# lcd.net
KiCad netlist of a schematic drawn in EAGLE
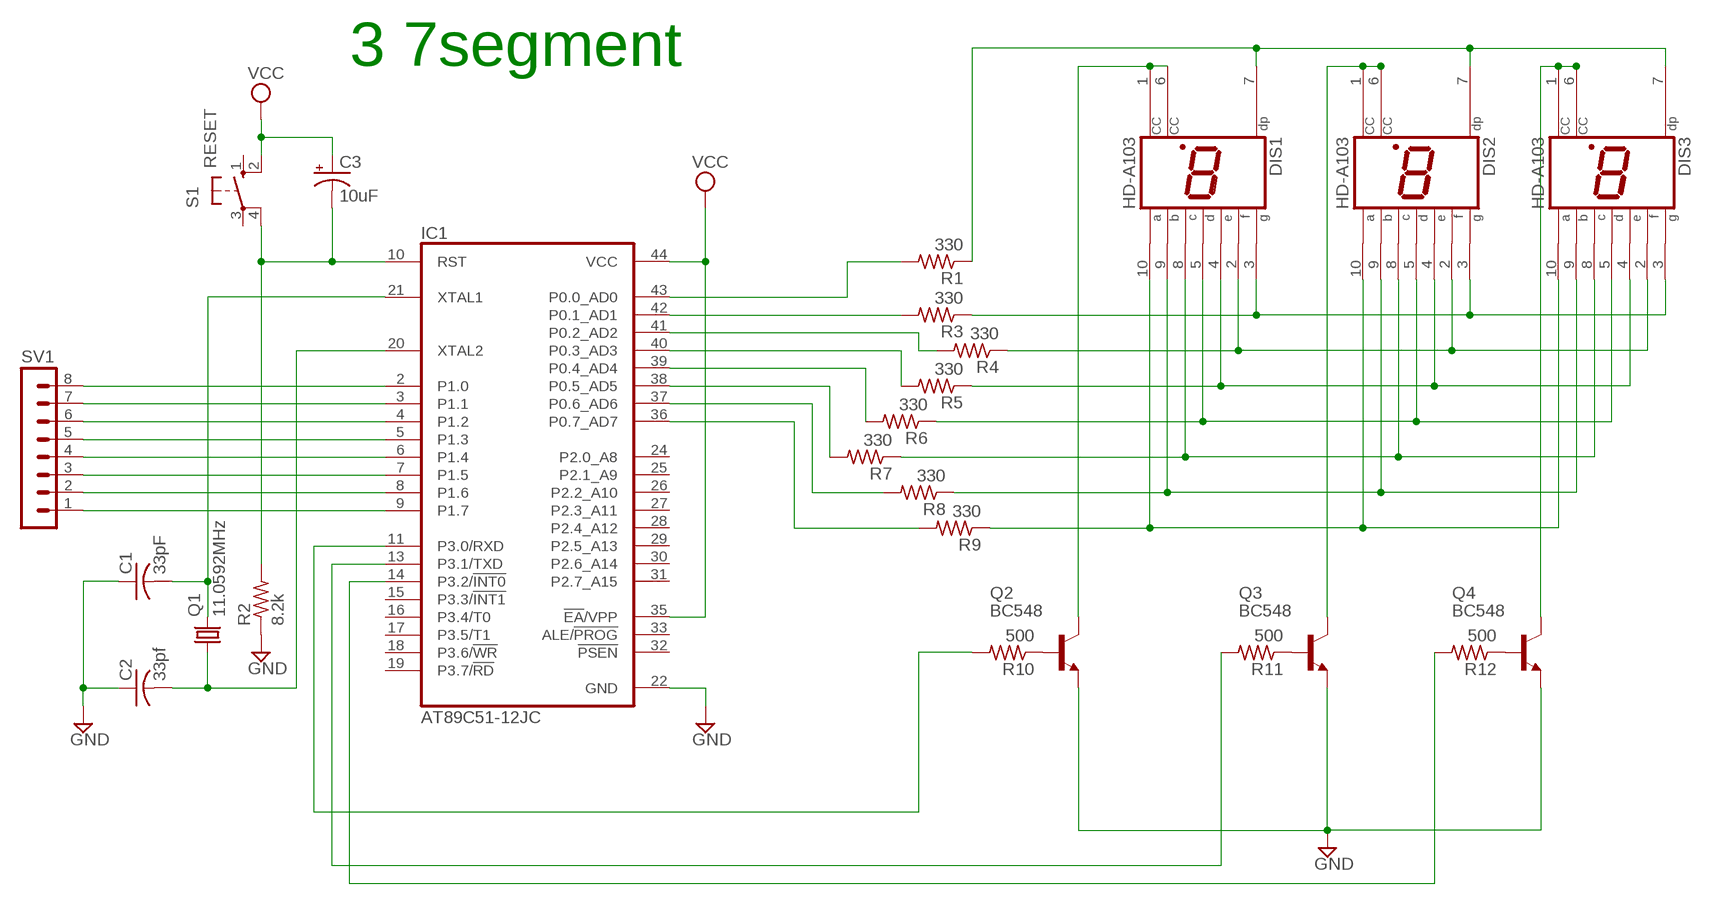
[diagram p0: schematic, sheet 1]

(export (version "E")
  (design (tool "Eeschema 10.0.6"))
  (components
    (comp (ref "C1")
      (value "33pF")
      (footprint "eagle-import:C025-025X050")
      (libsource (lib "eagle-import") (part "C-US025-025X050"))
    )
    (comp (ref "C2")
      (value "33pf")
      (footprint "eagle-import:C025-025X050")
      (libsource (lib "eagle-import") (part "C-US025-025X050"))
    )
    (comp (ref "C3")
      (value "10uF")
      (footprint "eagle-import:E2,5-5")
      (libsource (lib "eagle-import") (part "CPOL-USE2.5-5"))
    )
    (comp (ref "DIS1")
      (value "HD-A103")
      (footprint "eagle-import:HDSP-A")
      (libsource (lib "eagle-import") (part "HD-A103"))
    )
    (comp (ref "DIS2")
      (value "HD-A103")
      (footprint "eagle-import:HDSP-A")
      (libsource (lib "eagle-import") (part "HD-A103"))
    )
    (comp (ref "DIS3")
      (value "HD-A103")
      (footprint "eagle-import:HDSP-A")
      (libsource (lib "eagle-import") (part "HD-A103"))
    )
    (comp (ref "IC1")
      (value "AT89C51-12JC")
      (footprint "eagle-import:PLCC44")
      (fields (field (name "MPN") "AT89C51ED2-SLSUM"))
      (libsource (lib "eagle-import") (part "AT89C51-JC12"))
    )
    (comp (ref "Q1")
      (value "11.0592MHz")
      (footprint "eagle-import:TC26H")
      (libsource (lib "eagle-import") (part "CRYSTALTC26H"))
    )
    (comp (ref "Q2")
      (value "BC548")
      (footprint "eagle-import:TO92-EBC")
      (libsource (lib "eagle-import") (part "BC548"))
    )
    (comp (ref "Q3")
      (value "BC548")
      (footprint "eagle-import:TO92-EBC")
      (libsource (lib "eagle-import") (part "BC548"))
    )
    (comp (ref "Q4")
      (value "BC548")
      (footprint "eagle-import:TO92-EBC")
      (libsource (lib "eagle-import") (part "BC548"))
    )
    (comp (ref "R1")
      (value "330")
      (footprint "eagle-import:R2512")
      (libsource (lib "eagle-import") (part "R-US_R2512"))
    )
    (comp (ref "R2")
      (value "8.2k")
      (footprint "eagle-import:R2512")
      (libsource (lib "eagle-import") (part "R-US_R2512"))
    )
    (comp (ref "R3")
      (value "330")
      (footprint "eagle-import:R2512")
      (libsource (lib "eagle-import") (part "R-US_R2512"))
    )
    (comp (ref "R4")
      (value "330")
      (footprint "eagle-import:R2512")
      (libsource (lib "eagle-import") (part "R-US_R2512"))
    )
    (comp (ref "R5")
      (value "330")
      (footprint "eagle-import:R2512")
      (libsource (lib "eagle-import") (part "R-US_R2512"))
    )
    (comp (ref "R6")
      (value "330")
      (footprint "eagle-import:R2512")
      (libsource (lib "eagle-import") (part "R-US_R2512"))
    )
    (comp (ref "R7")
      (value "330")
      (footprint "eagle-import:R2512")
      (libsource (lib "eagle-import") (part "R-US_R2512"))
    )
    (comp (ref "R8")
      (value "330")
      (footprint "eagle-import:R2512")
      (libsource (lib "eagle-import") (part "R-US_R2512"))
    )
    (comp (ref "R9")
      (value "330")
      (footprint "eagle-import:R2512")
      (libsource (lib "eagle-import") (part "R-US_R2512"))
    )
    (comp (ref "R10")
      (value "500")
      (footprint "eagle-import:R2512")
      (libsource (lib "eagle-import") (part "R-US_R2512"))
    )
    (comp (ref "R11")
      (value "500")
      (footprint "eagle-import:R2512")
      (libsource (lib "eagle-import") (part "R-US_R2512"))
    )
    (comp (ref "R12")
      (value "500")
      (footprint "eagle-import:R2512")
      (libsource (lib "eagle-import") (part "R-US_R2512"))
    )
    (comp (ref "S1")
      (value "RESET")
      (footprint "eagle-import:B3F-10XX")
      (fields (field (name "MPN") "B3F-1000"))
      (libsource (lib "eagle-import") (part "10-XX"))
    )
    (comp (ref "SV1")
      (value "MA08-1W")
      (footprint "eagle-import:MA08-1W")
      (libsource (lib "eagle-import") (part "MA08-1W"))
    )
  )
  (nets
    (net (code "1") (name "GND") (class "Default")
      (node (ref "C1") (pin "1") (pinfunction "1_1") (pintype "passive"))
      (node (ref "C2") (pin "1") (pinfunction "1_1") (pintype "passive"))
      (node (ref "IC1") (pin "22") (pinfunction "GND_22") (pintype "power_in"))
      (node (ref "Q2") (pin "E") (pinfunction "E_E") (pintype "passive"))
      (node (ref "Q3") (pin "E") (pinfunction "E_E") (pintype "passive"))
      (node (ref "Q4") (pin "E") (pinfunction "E_E") (pintype "passive"))
      (node (ref "R2") (pin "1") (pinfunction "1_1") (pintype "passive"))
    )
    (net (code "2") (name "Net-(DIS1-A)") (class "Default")
      (node (ref "DIS1") (pin "10") (pinfunction "A_10") (pintype "passive"))
      (node (ref "DIS2") (pin "10") (pinfunction "A_10") (pintype "passive"))
      (node (ref "DIS3") (pin "10") (pinfunction "A_10") (pintype "passive"))
      (node (ref "R9") (pin "1") (pinfunction "1_1") (pintype "passive"))
    )
    (net (code "3") (name "Net-(DIS1-B)") (class "Default")
      (node (ref "DIS1") (pin "9") (pinfunction "B_9") (pintype "passive"))
      (node (ref "DIS2") (pin "9") (pinfunction "B_9") (pintype "passive"))
      (node (ref "DIS3") (pin "9") (pinfunction "B_9") (pintype "passive"))
      (node (ref "R8") (pin "1") (pinfunction "1_1") (pintype "passive"))
    )
    (net (code "4") (name "Net-(DIS1-C)") (class "Default")
      (node (ref "DIS1") (pin "8") (pinfunction "C_8") (pintype "passive"))
      (node (ref "DIS2") (pin "8") (pinfunction "C_8") (pintype "passive"))
      (node (ref "DIS3") (pin "8") (pinfunction "C_8") (pintype "passive"))
      (node (ref "R7") (pin "1") (pinfunction "1_1") (pintype "passive"))
    )
    (net (code "5") (name "Net-(DIS1-CC-Pad1)") (class "Default")
      (node (ref "DIS1") (pin "1") (pinfunction "CC_1") (pintype "passive"))
      (node (ref "DIS1") (pin "6") (pinfunction "CC_6") (pintype "passive"))
      (node (ref "Q2") (pin "C") (pinfunction "C_C") (pintype "passive"))
    )
    (net (code "6") (name "Net-(DIS1-D)") (class "Default")
      (node (ref "DIS1") (pin "5") (pinfunction "D_5") (pintype "passive"))
      (node (ref "DIS2") (pin "5") (pinfunction "D_5") (pintype "passive"))
      (node (ref "DIS3") (pin "5") (pinfunction "D_5") (pintype "passive"))
      (node (ref "R6") (pin "1") (pinfunction "1_1") (pintype "passive"))
    )
    (net (code "7") (name "Net-(DIS1-DP)") (class "Default")
      (node (ref "DIS1") (pin "7") (pinfunction "DP_7") (pintype "passive"))
      (node (ref "DIS2") (pin "7") (pinfunction "DP_7") (pintype "passive"))
      (node (ref "DIS3") (pin "7") (pinfunction "DP_7") (pintype "passive"))
      (node (ref "R1") (pin "1") (pinfunction "1_1") (pintype "passive"))
    )
    (net (code "8") (name "Net-(DIS1-E)") (class "Default")
      (node (ref "DIS1") (pin "4") (pinfunction "E_4") (pintype "passive"))
      (node (ref "DIS2") (pin "4") (pinfunction "E_4") (pintype "passive"))
      (node (ref "DIS3") (pin "4") (pinfunction "E_4") (pintype "passive"))
      (node (ref "R5") (pin "1") (pinfunction "1_1") (pintype "passive"))
    )
    (net (code "9") (name "Net-(DIS1-F)") (class "Default")
      (node (ref "DIS1") (pin "2") (pinfunction "F_2") (pintype "passive"))
      (node (ref "DIS2") (pin "2") (pinfunction "F_2") (pintype "passive"))
      (node (ref "DIS3") (pin "2") (pinfunction "F_2") (pintype "passive"))
      (node (ref "R4") (pin "1") (pinfunction "1_1") (pintype "passive"))
    )
    (net (code "10") (name "Net-(DIS1-G)") (class "Default")
      (node (ref "DIS1") (pin "3") (pinfunction "G_3") (pintype "passive"))
      (node (ref "DIS2") (pin "3") (pinfunction "G_3") (pintype "passive"))
      (node (ref "DIS3") (pin "3") (pinfunction "G_3") (pintype "passive"))
      (node (ref "R3") (pin "1") (pinfunction "1_1") (pintype "passive"))
    )
    (net (code "11") (name "Net-(DIS2-CC-Pad1)") (class "Default")
      (node (ref "DIS2") (pin "1") (pinfunction "CC_1") (pintype "passive"))
      (node (ref "DIS2") (pin "6") (pinfunction "CC_6") (pintype "passive"))
      (node (ref "Q3") (pin "C") (pinfunction "C_C") (pintype "passive"))
    )
    (net (code "12") (name "Net-(DIS3-CC-Pad1)") (class "Default")
      (node (ref "DIS3") (pin "1") (pinfunction "CC_1") (pintype "passive"))
      (node (ref "DIS3") (pin "6") (pinfunction "CC_6") (pintype "passive"))
      (node (ref "Q4") (pin "C") (pinfunction "C_C") (pintype "passive"))
    )
    (net (code "13") (name "Net-(IC1-P0.0_AD0)") (class "Default")
      (node (ref "IC1") (pin "43") (pinfunction "P0.0_AD0_43") (pintype "bidirectional"))
      (node (ref "R1") (pin "2") (pinfunction "2_2") (pintype "passive"))
    )
    (net (code "14") (name "Net-(IC1-P0.1_AD1)") (class "Default")
      (node (ref "IC1") (pin "42") (pinfunction "P0.1_AD1_42") (pintype "bidirectional"))
      (node (ref "R3") (pin "2") (pinfunction "2_2") (pintype "passive"))
    )
    (net (code "15") (name "Net-(IC1-P0.2_AD2)") (class "Default")
      (node (ref "IC1") (pin "41") (pinfunction "P0.2_AD2_41") (pintype "bidirectional"))
      (node (ref "R4") (pin "2") (pinfunction "2_2") (pintype "passive"))
    )
    (net (code "16") (name "Net-(IC1-P0.3_AD3)") (class "Default")
      (node (ref "IC1") (pin "40") (pinfunction "P0.3_AD3_40") (pintype "bidirectional"))
      (node (ref "R5") (pin "2") (pinfunction "2_2") (pintype "passive"))
    )
    (net (code "17") (name "Net-(IC1-P0.4_AD4)") (class "Default")
      (node (ref "IC1") (pin "39") (pinfunction "P0.4_AD4_39") (pintype "bidirectional"))
      (node (ref "R6") (pin "2") (pinfunction "2_2") (pintype "passive"))
    )
    (net (code "18") (name "Net-(IC1-P0.5_AD5)") (class "Default")
      (node (ref "IC1") (pin "38") (pinfunction "P0.5_AD5_38") (pintype "bidirectional"))
      (node (ref "R7") (pin "2") (pinfunction "2_2") (pintype "passive"))
    )
    (net (code "19") (name "Net-(IC1-P0.6_AD6)") (class "Default")
      (node (ref "IC1") (pin "37") (pinfunction "P0.6_AD6_37") (pintype "bidirectional"))
      (node (ref "R8") (pin "2") (pinfunction "2_2") (pintype "passive"))
    )
    (net (code "20") (name "Net-(IC1-P0.7_AD7)") (class "Default")
      (node (ref "IC1") (pin "36") (pinfunction "P0.7_AD7_36") (pintype "bidirectional"))
      (node (ref "R9") (pin "2") (pinfunction "2_2") (pintype "passive"))
    )
    (net (code "21") (name "Net-(IC1-P1.0)") (class "Default")
      (node (ref "IC1") (pin "2") (pinfunction "P1.0_2") (pintype "bidirectional"))
      (node (ref "SV1") (pin "8") (pinfunction "8_8") (pintype "passive"))
    )
    (net (code "22") (name "Net-(IC1-P1.1)") (class "Default")
      (node (ref "IC1") (pin "3") (pinfunction "P1.1_3") (pintype "bidirectional"))
      (node (ref "SV1") (pin "7") (pinfunction "7_7") (pintype "passive"))
    )
    (net (code "23") (name "Net-(IC1-P1.2)") (class "Default")
      (node (ref "IC1") (pin "4") (pinfunction "P1.2_4") (pintype "bidirectional"))
      (node (ref "SV1") (pin "6") (pinfunction "6_6") (pintype "passive"))
    )
    (net (code "24") (name "Net-(IC1-P1.3)") (class "Default")
      (node (ref "IC1") (pin "5") (pinfunction "P1.3_5") (pintype "bidirectional"))
      (node (ref "SV1") (pin "5") (pinfunction "5_5") (pintype "passive"))
    )
    (net (code "25") (name "Net-(IC1-P1.4)") (class "Default")
      (node (ref "IC1") (pin "6") (pinfunction "P1.4_6") (pintype "bidirectional"))
      (node (ref "SV1") (pin "4") (pinfunction "4_4") (pintype "passive"))
    )
    (net (code "26") (name "Net-(IC1-P1.5)") (class "Default")
      (node (ref "IC1") (pin "7") (pinfunction "P1.5_7") (pintype "bidirectional"))
      (node (ref "SV1") (pin "3") (pinfunction "3_3") (pintype "passive"))
    )
    (net (code "27") (name "Net-(IC1-P1.6)") (class "Default")
      (node (ref "IC1") (pin "8") (pinfunction "P1.6_8") (pintype "bidirectional"))
      (node (ref "SV1") (pin "2") (pinfunction "2_2") (pintype "passive"))
    )
    (net (code "28") (name "Net-(IC1-P1.7)") (class "Default")
      (node (ref "IC1") (pin "9") (pinfunction "P1.7_9") (pintype "bidirectional"))
      (node (ref "SV1") (pin "1") (pinfunction "1_1") (pintype "passive"))
    )
    (net (code "29") (name "Net-(IC1-P3.0{slash}RXD)") (class "Default")
      (node (ref "IC1") (pin "11") (pinfunction "P3.0/RXD_11") (pintype "bidirectional"))
      (node (ref "R10") (pin "2") (pinfunction "2_2") (pintype "passive"))
    )
    (net (code "30") (name "Net-(IC1-P3.1{slash}TXD)") (class "Default")
      (node (ref "IC1") (pin "13") (pinfunction "P3.1/TXD_13") (pintype "bidirectional"))
      (node (ref "R11") (pin "2") (pinfunction "2_2") (pintype "passive"))
    )
    (net (code "31") (name "Net-(IC1-P3.2{slash}~{INT0})") (class "Default")
      (node (ref "IC1") (pin "14") (pinfunction "P3.2/~{INT0}_14") (pintype "bidirectional"))
      (node (ref "R12") (pin "2") (pinfunction "2_2") (pintype "passive"))
    )
    (net (code "32") (name "Net-(IC1-RST)") (class "Default")
      (node (ref "C3") (pin "-") (pinfunction "-_-") (pintype "passive"))
      (node (ref "IC1") (pin "10") (pinfunction "RST_10") (pintype "input"))
      (node (ref "R2") (pin "2") (pinfunction "2_2") (pintype "passive"))
      (node (ref "S1") (pin "4") (pinfunction "P1_4") (pintype "passive"))
    )
    (net (code "33") (name "Net-(IC1-XTAL1)") (class "Default")
      (node (ref "C1") (pin "2") (pinfunction "2_2") (pintype "passive"))
      (node (ref "IC1") (pin "21") (pinfunction "XTAL1_21") (pintype "input"))
      (node (ref "Q1") (pin "2") (pinfunction "2_2") (pintype "passive"))
    )
    (net (code "34") (name "Net-(IC1-XTAL2)") (class "Default")
      (node (ref "C2") (pin "2") (pinfunction "2_2") (pintype "passive"))
      (node (ref "IC1") (pin "20") (pinfunction "XTAL2_20") (pintype "input"))
      (node (ref "Q1") (pin "1") (pinfunction "1_1") (pintype "passive"))
    )
    (net (code "35") (name "Net-(Q2-PadB)") (class "Default")
      (node (ref "Q2") (pin "B") (pinfunction "B_B") (pintype "passive"))
      (node (ref "R10") (pin "1") (pinfunction "1_1") (pintype "passive"))
    )
    (net (code "36") (name "Net-(Q3-PadB)") (class "Default")
      (node (ref "Q3") (pin "B") (pinfunction "B_B") (pintype "passive"))
      (node (ref "R11") (pin "1") (pinfunction "1_1") (pintype "passive"))
    )
    (net (code "37") (name "Net-(Q4-PadB)") (class "Default")
      (node (ref "Q4") (pin "B") (pinfunction "B_B") (pintype "passive"))
      (node (ref "R12") (pin "1") (pinfunction "1_1") (pintype "passive"))
    )
    (net (code "38") (name "VCC") (class "Default")
      (node (ref "C3") (pin "+") (pinfunction "+_+") (pintype "passive"))
      (node (ref "IC1") (pin "35") (pinfunction "~{EA}/VPP_35") (pintype "input"))
      (node (ref "IC1") (pin "44") (pinfunction "VCC_44") (pintype "power_in"))
      (node (ref "S1") (pin "2") (pinfunction "S1_2") (pintype "passive"))
    )
    (net (code "39") (name "unconnected-(IC1-ALE{slash}~{PROG}-Pad33)") (class "Default")
      (node (ref "IC1") (pin "33") (pinfunction "ALE/~{PROG}_33") (pintype "output"))
    )
    (net (code "40") (name "unconnected-(IC1-P2.0_A8-Pad24)") (class "Default")
      (node (ref "IC1") (pin "24") (pinfunction "P2.0_A8_24") (pintype "bidirectional"))
    )
    (net (code "41") (name "unconnected-(IC1-P2.1_A9-Pad25)") (class "Default")
      (node (ref "IC1") (pin "25") (pinfunction "P2.1_A9_25") (pintype "bidirectional"))
    )
    (net (code "42") (name "unconnected-(IC1-P2.2_A10-Pad26)") (class "Default")
      (node (ref "IC1") (pin "26") (pinfunction "P2.2_A10_26") (pintype "bidirectional"))
    )
    (net (code "43") (name "unconnected-(IC1-P2.3_A11-Pad27)") (class "Default")
      (node (ref "IC1") (pin "27") (pinfunction "P2.3_A11_27") (pintype "bidirectional"))
    )
    (net (code "44") (name "unconnected-(IC1-P2.4_A12-Pad28)") (class "Default")
      (node (ref "IC1") (pin "28") (pinfunction "P2.4_A12_28") (pintype "bidirectional"))
    )
    (net (code "45") (name "unconnected-(IC1-P2.5_A13-Pad29)") (class "Default")
      (node (ref "IC1") (pin "29") (pinfunction "P2.5_A13_29") (pintype "bidirectional"))
    )
    (net (code "46") (name "unconnected-(IC1-P2.6_A14-Pad30)") (class "Default")
      (node (ref "IC1") (pin "30") (pinfunction "P2.6_A14_30") (pintype "bidirectional"))
    )
    (net (code "47") (name "unconnected-(IC1-P2.7_A15-Pad31)") (class "Default")
      (node (ref "IC1") (pin "31") (pinfunction "P2.7_A15_31") (pintype "bidirectional"))
    )
    (net (code "48") (name "unconnected-(IC1-P3.3{slash}~{INT1}-Pad15)") (class "Default")
      (node (ref "IC1") (pin "15") (pinfunction "P3.3/~{INT1}_15") (pintype "bidirectional"))
    )
    (net (code "49") (name "unconnected-(IC1-P3.4{slash}T0-Pad16)") (class "Default")
      (node (ref "IC1") (pin "16") (pinfunction "P3.4/T0_16") (pintype "bidirectional"))
    )
    (net (code "50") (name "unconnected-(IC1-P3.5{slash}T1-Pad17)") (class "Default")
      (node (ref "IC1") (pin "17") (pinfunction "P3.5/T1_17") (pintype "bidirectional"))
    )
    (net (code "51") (name "unconnected-(IC1-P3.6{slash}~{WR}-Pad18)") (class "Default")
      (node (ref "IC1") (pin "18") (pinfunction "P3.6/~{WR}_18") (pintype "bidirectional"))
    )
    (net (code "52") (name "unconnected-(IC1-P3.7{slash}~{RD}-Pad19)") (class "Default")
      (node (ref "IC1") (pin "19") (pinfunction "P3.7/~{RD}_19") (pintype "bidirectional"))
    )
    (net (code "53") (name "unconnected-(IC1-~{PSEN}-Pad32)") (class "Default")
      (node (ref "IC1") (pin "32") (pinfunction "~{PSEN}_32") (pintype "output"))
    )
    (net (code "54") (name "unconnected-(S1-P-Pad3)") (class "Default")
      (node (ref "S1") (pin "3") (pinfunction "P_3") (pintype "passive"))
    )
    (net (code "55") (name "unconnected-(S1-S-Pad1)") (class "Default")
      (node (ref "S1") (pin "1") (pinfunction "S_1") (pintype "passive"))
    )
  )
)
